# UniDCDC_asch.net
KiCad netlist of a schematic drawn in EAGLE
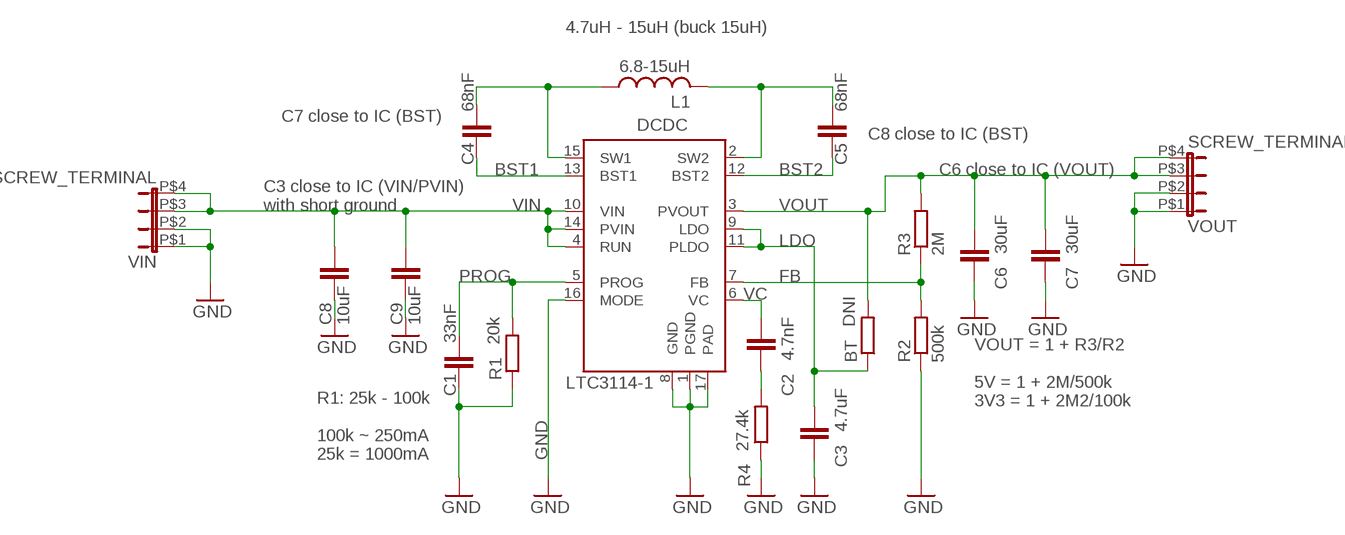
[diagram p0: schematic, sheet 1]

(export (version "E")
  (design (tool "Eeschema 10.0.6"))
  (components
    (comp (ref "BT")
      (value "DNI")
      (footprint "eagle-import:R0805")
      (libsource (lib "eagle-import") (part "R-EU_R0805"))
    )
    (comp (ref "C1")
      (value "33nF")
      (footprint "eagle-import:C0805K")
      (libsource (lib "eagle-import") (part "C-EUC0805K"))
    )
    (comp (ref "C2")
      (value "4.7nF")
      (footprint "eagle-import:C0805K")
      (libsource (lib "eagle-import") (part "C-EUC0805K"))
    )
    (comp (ref "C3")
      (value "4.7uF")
      (footprint "eagle-import:C0805K")
      (libsource (lib "eagle-import") (part "C-EUC0805K"))
    )
    (comp (ref "C4")
      (value "68nF")
      (footprint "eagle-import:C0805K")
      (libsource (lib "eagle-import") (part "C-EUC0805K"))
    )
    (comp (ref "C5")
      (value "68nF")
      (footprint "eagle-import:C0805K")
      (libsource (lib "eagle-import") (part "C-EUC0805K"))
    )
    (comp (ref "C6")
      (value "30uF")
      (footprint "eagle-import:C0805K")
      (libsource (lib "eagle-import") (part "C-EUC0805K"))
    )
    (comp (ref "C7")
      (value "30uF")
      (footprint "eagle-import:C0805K")
      (libsource (lib "eagle-import") (part "C-EUC0805K"))
    )
    (comp (ref "C8")
      (value "10uF")
      (footprint "eagle-import:C0805K")
      (libsource (lib "eagle-import") (part "C-EUC0805K"))
    )
    (comp (ref "C9")
      (value "10uF")
      (footprint "eagle-import:C0805K")
      (libsource (lib "eagle-import") (part "C-EUC0805K"))
    )
    (comp (ref "DCDC")
      (value "LTC3114-1")
      (footprint "eagle-import:TSSOP16")
      (libsource (lib "eagle-import") (part "LTC3114-1"))
    )
    (comp (ref "L1")
      (value "6.8-15uH")
      (footprint "eagle-import:MSS1278_SMD")
      (libsource (lib "eagle-import") (part "MSS1278"))
    )
    (comp (ref "R1")
      (value "20k")
      (footprint "eagle-import:R0805")
      (libsource (lib "eagle-import") (part "R-EU_R0805"))
    )
    (comp (ref "R2")
      (value "500k")
      (footprint "eagle-import:R0805")
      (libsource (lib "eagle-import") (part "R-EU_R0805"))
    )
    (comp (ref "R3")
      (value "2M")
      (footprint "eagle-import:R0805")
      (libsource (lib "eagle-import") (part "R-EU_R0805"))
    )
    (comp (ref "R4")
      (value "27.4k")
      (footprint "eagle-import:R0805")
      (libsource (lib "eagle-import") (part "R-EU_R0805"))
    )
    (comp (ref "VIN")
      (value "SCREW_TERMINAL")
      (footprint "eagle-import:SCREW_TERMINAL")
      (libsource (lib "eagle-import") (part "SCREW_TERMINAL"))
    )
    (comp (ref "VOUT")
      (value "SCREW_TERMINAL")
      (footprint "eagle-import:SCREW_TERMINAL")
      (libsource (lib "eagle-import") (part "SCREW_TERMINAL"))
    )
  )
  (nets
    (net (code "1") (name "/BST1") (class "Default")
      (node (ref "C4") (pin "2") (pinfunction "2_2") (pintype "passive"))
      (node (ref "DCDC") (pin "13") (pinfunction "BST1_13") (pintype "input"))
    )
    (net (code "2") (name "/BST2") (class "Default")
      (node (ref "C5") (pin "2") (pinfunction "2_2") (pintype "passive"))
      (node (ref "DCDC") (pin "12") (pinfunction "BST2_12") (pintype "passive"))
    )
    (net (code "3") (name "/FB") (class "Default")
      (node (ref "DCDC") (pin "7") (pinfunction "FB_7") (pintype "input"))
      (node (ref "R2") (pin "2") (pinfunction "2_2") (pintype "passive"))
      (node (ref "R3") (pin "1") (pinfunction "1_1") (pintype "passive"))
    )
    (net (code "4") (name "/LDO") (class "Default")
      (node (ref "BT") (pin "1") (pinfunction "1_1") (pintype "passive"))
      (node (ref "C3") (pin "1") (pinfunction "1_1") (pintype "passive"))
      (node (ref "DCDC") (pin "11") (pinfunction "PLDO_11") (pintype "input"))
      (node (ref "DCDC") (pin "9") (pinfunction "LDO_9") (pintype "input"))
    )
    (net (code "5") (name "/PROG") (class "Default")
      (node (ref "C1") (pin "1") (pinfunction "1_1") (pintype "passive"))
      (node (ref "DCDC") (pin "5") (pinfunction "PROG_5") (pintype "passive"))
      (node (ref "R1") (pin "2") (pinfunction "2_2") (pintype "passive"))
    )
    (net (code "6") (name "/VC") (class "Default")
      (node (ref "C2") (pin "1") (pinfunction "1_1") (pintype "passive"))
      (node (ref "DCDC") (pin "6") (pinfunction "VC_6") (pintype "input"))
    )
    (net (code "7") (name "/VIN") (class "Default")
      (node (ref "C8") (pin "1") (pinfunction "1_1") (pintype "passive"))
      (node (ref "C9") (pin "1") (pinfunction "1_1") (pintype "passive"))
      (node (ref "DCDC") (pin "10") (pinfunction "VIN_10") (pintype "open_collector"))
      (node (ref "DCDC") (pin "14") (pinfunction "PVIN_14") (pintype "input"))
      (node (ref "DCDC") (pin "4") (pinfunction "RUN_4") (pintype "passive"))
      (node (ref "VIN") (pin "P$3") (pinfunction "3_P$3") (pintype "passive"))
      (node (ref "VIN") (pin "P$4") (pinfunction "4_P$4") (pintype "passive"))
    )
    (net (code "8") (name "/VOUT") (class "Default")
      (node (ref "BT") (pin "2") (pinfunction "2_2") (pintype "passive"))
      (node (ref "C6") (pin "1") (pinfunction "1_1") (pintype "passive"))
      (node (ref "C7") (pin "1") (pinfunction "1_1") (pintype "passive"))
      (node (ref "DCDC") (pin "3") (pinfunction "PVOUT_3") (pintype "input"))
      (node (ref "R3") (pin "2") (pinfunction "2_2") (pintype "passive"))
      (node (ref "VOUT") (pin "P$3") (pinfunction "3_P$3") (pintype "passive"))
      (node (ref "VOUT") (pin "P$4") (pinfunction "4_P$4") (pintype "passive"))
    )
    (net (code "9") (name "GND") (class "Default")
      (node (ref "C1") (pin "2") (pinfunction "2_2") (pintype "passive"))
      (node (ref "C3") (pin "2") (pinfunction "2_2") (pintype "passive"))
      (node (ref "C6") (pin "2") (pinfunction "2_2") (pintype "passive"))
      (node (ref "C7") (pin "2") (pinfunction "2_2") (pintype "passive"))
      (node (ref "C8") (pin "2") (pinfunction "2_2") (pintype "passive"))
      (node (ref "C9") (pin "2") (pinfunction "2_2") (pintype "passive"))
      (node (ref "DCDC") (pin "1") (pinfunction "PGND_1") (pintype "power_in"))
      (node (ref "DCDC") (pin "16") (pinfunction "MODE_16") (pintype "passive"))
      (node (ref "DCDC") (pin "17") (pinfunction "PAD_17") (pintype "power_in"))
      (node (ref "DCDC") (pin "8") (pinfunction "GND_8") (pintype "power_in"))
      (node (ref "R1") (pin "1") (pinfunction "1_1") (pintype "passive"))
      (node (ref "R2") (pin "1") (pinfunction "1_1") (pintype "passive"))
      (node (ref "R4") (pin "1") (pinfunction "1_1") (pintype "passive"))
      (node (ref "VIN") (pin "P$1") (pinfunction "1_P$1") (pintype "passive"))
      (node (ref "VIN") (pin "P$2") (pinfunction "2_P$2") (pintype "passive"))
      (node (ref "VOUT") (pin "P$1") (pinfunction "1_P$1") (pintype "passive"))
      (node (ref "VOUT") (pin "P$2") (pinfunction "2_P$2") (pintype "passive"))
    )
    (net (code "10") (name "Net-(C2-Pad2)") (class "Default")
      (node (ref "C2") (pin "2") (pinfunction "2_2") (pintype "passive"))
      (node (ref "R4") (pin "2") (pinfunction "2_2") (pintype "passive"))
    )
    (net (code "11") (name "Net-(DCDC-SW1)") (class "Default")
      (node (ref "C4") (pin "1") (pinfunction "1_1") (pintype "passive"))
      (node (ref "DCDC") (pin "15") (pinfunction "SW1_15") (pintype "power_in"))
      (node (ref "L1") (pin "P$1") (pinfunction "1_P$1") (pintype "passive"))
    )
    (net (code "12") (name "Net-(DCDC-SW2)") (class "Default")
      (node (ref "C5") (pin "1") (pinfunction "1_1") (pintype "passive"))
      (node (ref "DCDC") (pin "2") (pinfunction "SW2_2") (pintype "open_collector"))
      (node (ref "L1") (pin "P$2") (pinfunction "2_P$2") (pintype "passive"))
    )
  )
)
